# TPS53319_5_0V_Buck_Converter.net
KiCad netlist of a schematic drawn in Altium Designer
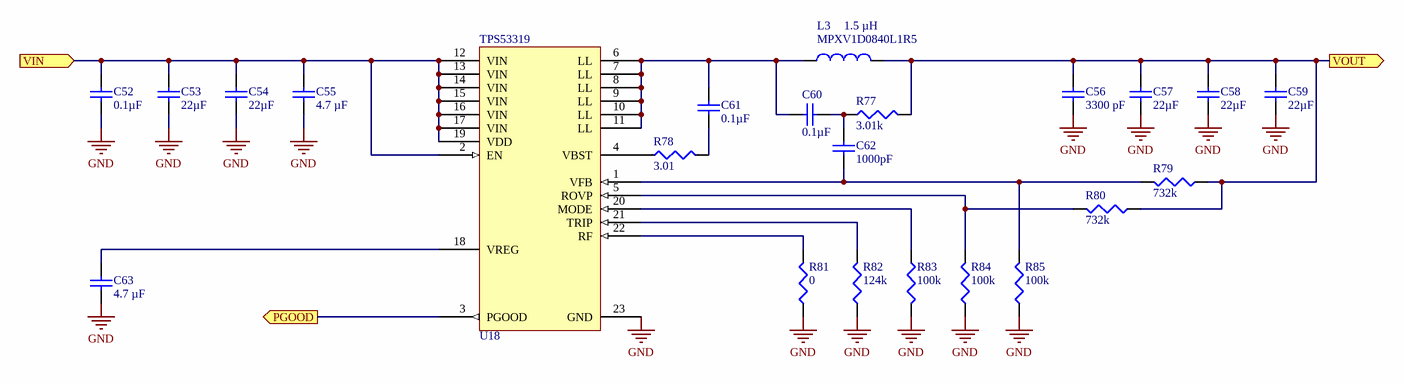
[diagram p0: TPS53319 5.0V Buck Converter.SchDoc]

(export (version "E")
  (design (tool "Eeschema 10.0.6"))
  (components
    (comp (ref "C52")
      (value "0.1µF")
      (footprint "TY-TWK107")
      (description "CAP CER 0.1UF 25V X7R 0306")
      (fields
        (field (name "PART NUMBER") "PC-TY-00817")
        (field (name "MANUFACTURER PART NUMBER") "TWK107B7104MVHT")
        (field (name "PUBLISHER") "AlbertaSat")
      )
      (libsource (lib "Database") (part "Cap"))
    )
    (comp (ref "C53")
      (value "22µF")
      (footprint "TDK-C3225")
      (description "CAP CER 22UF 25V X7R 1210")
      (fields
        (field (name "PART NUMBER") "PC-TDK-02965")
        (field (name "MANUFACTURER PART NUMBER") "C3225X7R1E226M250AB")
        (field (name "PUBLISHER") "AlbertaSat")
      )
      (libsource (lib "Database") (part "Cap"))
    )
    (comp (ref "C54")
      (value "22µF")
      (footprint "TDK-C3225")
      (description "CAP CER 22UF 25V X7R 1210")
      (fields
        (field (name "PART NUMBER") "PC-TDK-02965")
        (field (name "MANUFACTURER PART NUMBER") "C3225X7R1E226M250AB")
        (field (name "PUBLISHER") "AlbertaSat")
      )
      (libsource (lib "Database") (part "Cap"))
    )
    (comp (ref "C55")
      (value "4.7 µF")
      (footprint "MUR-GRM188")
      (description "CAP CER 4.7UF 16V X7R 0603")
      (fields
        (field (name "PART NUMBER") "10165")
        (field (name "MANUFACTURER PART NUMBER") "GRM188Z71C475KE21D")
        (field (name "PUBLISHER") "Altium Limited")
      )
      (libsource (lib "Database") (part "Cap"))
    )
    (comp (ref "C56")
      (value "3300 pF")
      (footprint "KEM-0402BB")
      (description "CAP CER 3300PF 50V X7R 0402")
      (fields
        (field (name "PART NUMBER") "PC-KEM-03166")
        (field (name "MANUFACTURER PART NUMBER") "C0402C332K5RAC7867")
        (field (name "PUBLISHER") "AlbertaSat")
      )
      (libsource (lib "Database") (part "Cap"))
    )
    (comp (ref "C57")
      (value "22µF")
      (footprint "TDK-C3225")
      (description "CAP CER 22UF 25V X7R 1210")
      (fields
        (field (name "PART NUMBER") "PC-TDK-02965")
        (field (name "MANUFACTURER PART NUMBER") "C3225X7R1E226M250AB")
        (field (name "PUBLISHER") "AlbertaSat")
      )
      (libsource (lib "Database") (part "Cap"))
    )
    (comp (ref "C58")
      (value "22µF")
      (footprint "TDK-C3225")
      (description "CAP CER 22UF 25V X7R 1210")
      (fields
        (field (name "PART NUMBER") "PC-TDK-02965")
        (field (name "MANUFACTURER PART NUMBER") "C3225X7R1E226M250AB")
        (field (name "PUBLISHER") "AlbertaSat")
      )
      (libsource (lib "Database") (part "Cap"))
    )
    (comp (ref "C59")
      (value "22µF")
      (footprint "TDK-C3225")
      (description "CAP CER 22UF 25V X7R 1210")
      (fields
        (field (name "PART NUMBER") "PC-TDK-02965")
        (field (name "MANUFACTURER PART NUMBER") "C3225X7R1E226M250AB")
        (field (name "PUBLISHER") "AlbertaSat")
      )
      (libsource (lib "Database") (part "Cap"))
    )
    (comp (ref "C60")
      (value "0.1µF")
      (footprint "TY-TWK107")
      (description "CAP CER 0.1UF 25V X7R 0306")
      (fields
        (field (name "PART NUMBER") "PC-TY-00817")
        (field (name "MANUFACTURER PART NUMBER") "TWK107B7104MVHT")
        (field (name "PUBLISHER") "AlbertaSat")
      )
      (libsource (lib "Database") (part "Cap"))
    )
    (comp (ref "C61")
      (value "0.1µF")
      (footprint "TY-TWK107")
      (description "CAP CER 0.1UF 25V X7R 0306")
      (fields
        (field (name "PART NUMBER") "PC-TY-00817")
        (field (name "MANUFACTURER PART NUMBER") "TWK107B7104MVHT")
        (field (name "PUBLISHER") "AlbertaSat")
      )
      (libsource (lib "Database") (part "Cap"))
    )
    (comp (ref "C62")
      (value "1000pF")
      (footprint "TDK-CGA2B")
      (description "CAP CER 1000PF 100V C0G 0402")
      (fields
        (field (name "PART NUMBER") "PC-TDK-01454")
        (field (name "MANUFACTURER PART NUMBER") "CGA2B1C0G2A102J050BC")
        (field (name "PUBLISHER") "AlbertaSat")
      )
      (libsource (lib "Database") (part "Cap"))
    )
    (comp (ref "C63")
      (value "4.7 µF")
      (footprint "MUR-GRM188")
      (description "CAP CER 4.7UF 16V X7R 0603")
      (fields
        (field (name "PART NUMBER") "10165")
        (field (name "MANUFACTURER PART NUMBER") "GRM188Z71C475KE21D")
        (field (name "PUBLISHER") "Altium Limited")
      )
      (libsource (lib "Database") (part "Cap"))
    )
    (comp (ref "L3")
      (value "1.5 µH")
      (footprint "KEM-MPXV1D0840")
      (description "FIXED IND 1.5UH 16.2A 6.8MOHM SM")
      (fields
        (field (name "PART NUMBER") "PL-KEM-03165")
        (field (name "MANUFACTURER PART NUMBER") "MPXV1D0840L1R5")
        (field (name "TOLERANCE") "±20%")
        (field (name "PUBLISHER") "AlbertaSat")
      )
      (libsource (lib "Database") (part "Inductor"))
    )
    (comp (ref "R77")
      (value "3.01k")
      (footprint "VSH-CRCW0201")
      (description "RES SMD 3.01K OHM 1% 1/20W 0201")
      (fields
        (field (name "PART NUMBER") "PR-VSH-00325")
        (field (name "MANUFACTURER PART NUMBER") "CRCW02013K01FKED")
        (field (name "PUBLISHER") "AlbertaSat")
      )
      (libsource (lib "Database") (part "Res3"))
    )
    (comp (ref "R78")
      (value "3.01")
      (footprint "VSH-CRCW0201")
      (description "CRCW0201 - 200/+400 3R01 1% ET7")
      (fields
        (field (name "PART NUMBER") "PR-VSH-00326")
        (field (name "MANUFACTURER PART NUMBER") "CRCW02013R01FXED")
        (field (name "PUBLISHER") "AlbertaSat")
      )
      (libsource (lib "Database") (part "Res3"))
    )
    (comp (ref "R79")
      (value "732k")
      (footprint "PANA-ERJ2R")
      (description "RES SMD 732K OHM 1% 1/10W 0402")
      (fields
        (field (name "PART NUMBER") "19585")
        (field (name "MANUFACTURER PART NUMBER") "ERJ-2RKF7323X")
        (field (name "PUBLISHER") "Altium Limited")
      )
      (libsource (lib "Database") (part "Res3"))
    )
    (comp (ref "R80")
      (value "732k")
      (footprint "PANA-ERJ2R")
      (description "RES SMD 732K OHM 1% 1/10W 0402")
      (fields
        (field (name "PART NUMBER") "19585")
        (field (name "MANUFACTURER PART NUMBER") "ERJ-2RKF7323X")
        (field (name "PUBLISHER") "Altium Limited")
      )
      (libsource (lib "Database") (part "Res3"))
    )
    (comp (ref "R81")
      (value "0")
      (footprint "PANA-ERJ2G")
      (description "RES SMD 0.0OHM JUMPER 1/10W 0402")
      (fields (field (name "PART NUMBER") "13127") (field (name "MANUFACTURER PART NUMBER") "ERJ-2GE0R00X"))
      (libsource (lib "Database") (part "Jumper3"))
    )
    (comp (ref "R82")
      (value "124k")
      (footprint "PANA-ERJ2R")
      (description "RES SMD 124K OHM 1% 1/10W 0402")
      (fields
        (field (name "PART NUMBER") "18840")
        (field (name "MANUFACTURER PART NUMBER") "ERJ-2RKF1243X")
        (field (name "PUBLISHER") "Altium Limited")
      )
      (libsource (lib "Database") (part "Res3"))
    )
    (comp (ref "R83")
      (value "100k")
      (footprint "PANA-ERJ2R")
      (description "RES SMD 100K OHM 1% 1/10W 0402")
      (fields
        (field (name "PART NUMBER") "18739")
        (field (name "MANUFACTURER PART NUMBER") "ERJ-2RKF1003X")
        (field (name "PUBLISHER") "Altium Limited")
      )
      (libsource (lib "Database") (part "Res3"))
    )
    (comp (ref "R84")
      (value "100k")
      (footprint "PANA-ERJ2R")
      (description "RES SMD 100K OHM 1% 1/10W 0402")
      (fields
        (field (name "PART NUMBER") "18739")
        (field (name "MANUFACTURER PART NUMBER") "ERJ-2RKF1003X")
        (field (name "PUBLISHER") "Altium Limited")
      )
      (libsource (lib "Database") (part "Res3"))
    )
    (comp (ref "R85")
      (value "100k")
      (footprint "PANA-ERJ2R")
      (description "RES SMD 100K OHM 1% 1/10W 0402")
      (fields
        (field (name "PART NUMBER") "18739")
        (field (name "MANUFACTURER PART NUMBER") "ERJ-2RKF1003X")
        (field (name "PUBLISHER") "Altium Limited")
      )
      (libsource (lib "Database") (part "Res3"))
    )
    (comp (ref "U18")
      (value "TPS53319")
      (footprint "TI-R-PSON-N22")
      (description "IC REG BUCK ADJUSTABLE 14A 22SON")
      (fields (field (name "PART NUMBER") "145") (field (name "MANUFACTURER PART NUMBER") "TPS53319DQPT"))
      (libsource (lib "Database") (part "TPS53319DQPT"))
    )
  )
  (nets
    (net (code "1") (name "/PGOOD") (class "Default")
      (node (ref "U18") (pin "3") (pinfunction "PGOOD_3") (pintype "output"))
    )
    (net (code "2") (name "/VIN") (class "Default")
      (node (ref "C52") (pin "2") (pinfunction "2_2") (pintype "passive"))
      (node (ref "C53") (pin "2") (pinfunction "2_2") (pintype "passive"))
      (node (ref "C54") (pin "2") (pinfunction "2_2") (pintype "passive"))
      (node (ref "C55") (pin "2") (pinfunction "2_2") (pintype "passive"))
      (node (ref "U18") (pin "12") (pinfunction "VIN_12") (pintype "power_in"))
      (node (ref "U18") (pin "13") (pinfunction "VIN_13") (pintype "power_in"))
      (node (ref "U18") (pin "14") (pinfunction "VIN_14") (pintype "power_in"))
      (node (ref "U18") (pin "15") (pinfunction "VIN_15") (pintype "power_in"))
      (node (ref "U18") (pin "16") (pinfunction "VIN_16") (pintype "power_in"))
      (node (ref "U18") (pin "17") (pinfunction "VIN_17") (pintype "power_in"))
      (node (ref "U18") (pin "19") (pinfunction "VDD_19") (pintype "power_in"))
      (node (ref "U18") (pin "2") (pinfunction "EN_2") (pintype "input"))
    )
    (net (code "3") (name "/VOUT") (class "Default")
      (node (ref "C56") (pin "2") (pinfunction "2_2") (pintype "passive"))
      (node (ref "C57") (pin "2") (pinfunction "2_2") (pintype "passive"))
      (node (ref "C58") (pin "2") (pinfunction "2_2") (pintype "passive"))
      (node (ref "C59") (pin "2") (pinfunction "2_2") (pintype "passive"))
      (node (ref "L3") (pin "2") (pinfunction "2_2") (pintype "passive"))
      (node (ref "R77") (pin "2") (pinfunction "2_2") (pintype "passive"))
      (node (ref "R79") (pin "1") (pinfunction "1_1") (pintype "passive"))
      (node (ref "R80") (pin "1") (pinfunction "1_1") (pintype "passive"))
    )
    (net (code "4") (name "GND") (class "Default")
      (node (ref "C52") (pin "1") (pinfunction "1_1") (pintype "passive"))
      (node (ref "C53") (pin "1") (pinfunction "1_1") (pintype "passive"))
      (node (ref "C54") (pin "1") (pinfunction "1_1") (pintype "passive"))
      (node (ref "C55") (pin "1") (pinfunction "1_1") (pintype "passive"))
      (node (ref "C56") (pin "1") (pinfunction "1_1") (pintype "passive"))
      (node (ref "C57") (pin "1") (pinfunction "1_1") (pintype "passive"))
      (node (ref "C58") (pin "1") (pinfunction "1_1") (pintype "passive"))
      (node (ref "C59") (pin "1") (pinfunction "1_1") (pintype "passive"))
      (node (ref "C63") (pin "1") (pinfunction "1_1") (pintype "passive"))
      (node (ref "R81") (pin "1") (pinfunction "1_1") (pintype "passive"))
      (node (ref "R82") (pin "1") (pinfunction "1_1") (pintype "passive"))
      (node (ref "R83") (pin "1") (pinfunction "1_1") (pintype "passive"))
      (node (ref "R84") (pin "1") (pinfunction "1_1") (pintype "passive"))
      (node (ref "R85") (pin "1") (pinfunction "1_1") (pintype "passive"))
      (node (ref "U18") (pin "23") (pinfunction "GND_23") (pintype "power_in"))
    )
    (net (code "5") (name "Net-(C60-Pad1)") (class "Default")
      (node (ref "C60") (pin "1") (pinfunction "1_1") (pintype "passive"))
      (node (ref "C62") (pin "1") (pinfunction "1_1") (pintype "passive"))
      (node (ref "R77") (pin "1") (pinfunction "1_1") (pintype "passive"))
    )
    (net (code "6") (name "Net-(C60-Pad2)") (class "Default")
      (node (ref "C60") (pin "2") (pinfunction "2_2") (pintype "passive"))
      (node (ref "C61") (pin "2") (pinfunction "2_2") (pintype "passive"))
      (node (ref "L3") (pin "1") (pinfunction "1_1") (pintype "passive"))
      (node (ref "U18") (pin "10") (pinfunction "LL_10") (pintype "power_in"))
      (node (ref "U18") (pin "11") (pinfunction "LL_11") (pintype "power_in"))
      (node (ref "U18") (pin "6") (pinfunction "LL_6") (pintype "power_in"))
      (node (ref "U18") (pin "7") (pinfunction "LL_7") (pintype "power_in"))
      (node (ref "U18") (pin "8") (pinfunction "LL_8") (pintype "power_in"))
      (node (ref "U18") (pin "9") (pinfunction "LL_9") (pintype "power_in"))
    )
    (net (code "7") (name "Net-(C61-Pad1)") (class "Default")
      (node (ref "C61") (pin "1") (pinfunction "1_1") (pintype "passive"))
      (node (ref "R78") (pin "2") (pinfunction "2_2") (pintype "passive"))
    )
    (net (code "8") (name "Net-(U18-MODE)") (class "Default")
      (node (ref "R83") (pin "2") (pinfunction "2_2") (pintype "passive"))
      (node (ref "U18") (pin "20") (pinfunction "MODE_20") (pintype "input"))
    )
    (net (code "9") (name "Net-(U18-RF)") (class "Default")
      (node (ref "R81") (pin "2") (pinfunction "2_2") (pintype "passive"))
      (node (ref "U18") (pin "22") (pinfunction "RF_22") (pintype "input"))
    )
    (net (code "10") (name "Net-(U18-ROVP)") (class "Default")
      (node (ref "R80") (pin "2") (pinfunction "2_2") (pintype "passive"))
      (node (ref "R84") (pin "2") (pinfunction "2_2") (pintype "passive"))
      (node (ref "U18") (pin "5") (pinfunction "ROVP_5") (pintype "input"))
    )
    (net (code "11") (name "Net-(U18-TRIP)") (class "Default")
      (node (ref "R82") (pin "2") (pinfunction "2_2") (pintype "passive"))
      (node (ref "U18") (pin "21") (pinfunction "TRIP_21") (pintype "input"))
    )
    (net (code "12") (name "Net-(U18-VBST)") (class "Default")
      (node (ref "R78") (pin "1") (pinfunction "1_1") (pintype "passive"))
      (node (ref "U18") (pin "4") (pinfunction "VBST_4") (pintype "power_in"))
    )
    (net (code "13") (name "Net-(U18-VFB)") (class "Default")
      (node (ref "C62") (pin "2") (pinfunction "2_2") (pintype "passive"))
      (node (ref "R79") (pin "2") (pinfunction "2_2") (pintype "passive"))
      (node (ref "R85") (pin "2") (pinfunction "2_2") (pintype "passive"))
      (node (ref "U18") (pin "1") (pinfunction "VFB_1") (pintype "input"))
    )
    (net (code "14") (name "Net-(U18-VREG)") (class "Default")
      (node (ref "C63") (pin "2") (pinfunction "2_2") (pintype "passive"))
      (node (ref "U18") (pin "18") (pinfunction "VREG_18") (pintype "passive"))
    )
  )
)
